# Acc_Comp.net
KiCad netlist of a schematic drawn in EAGLE
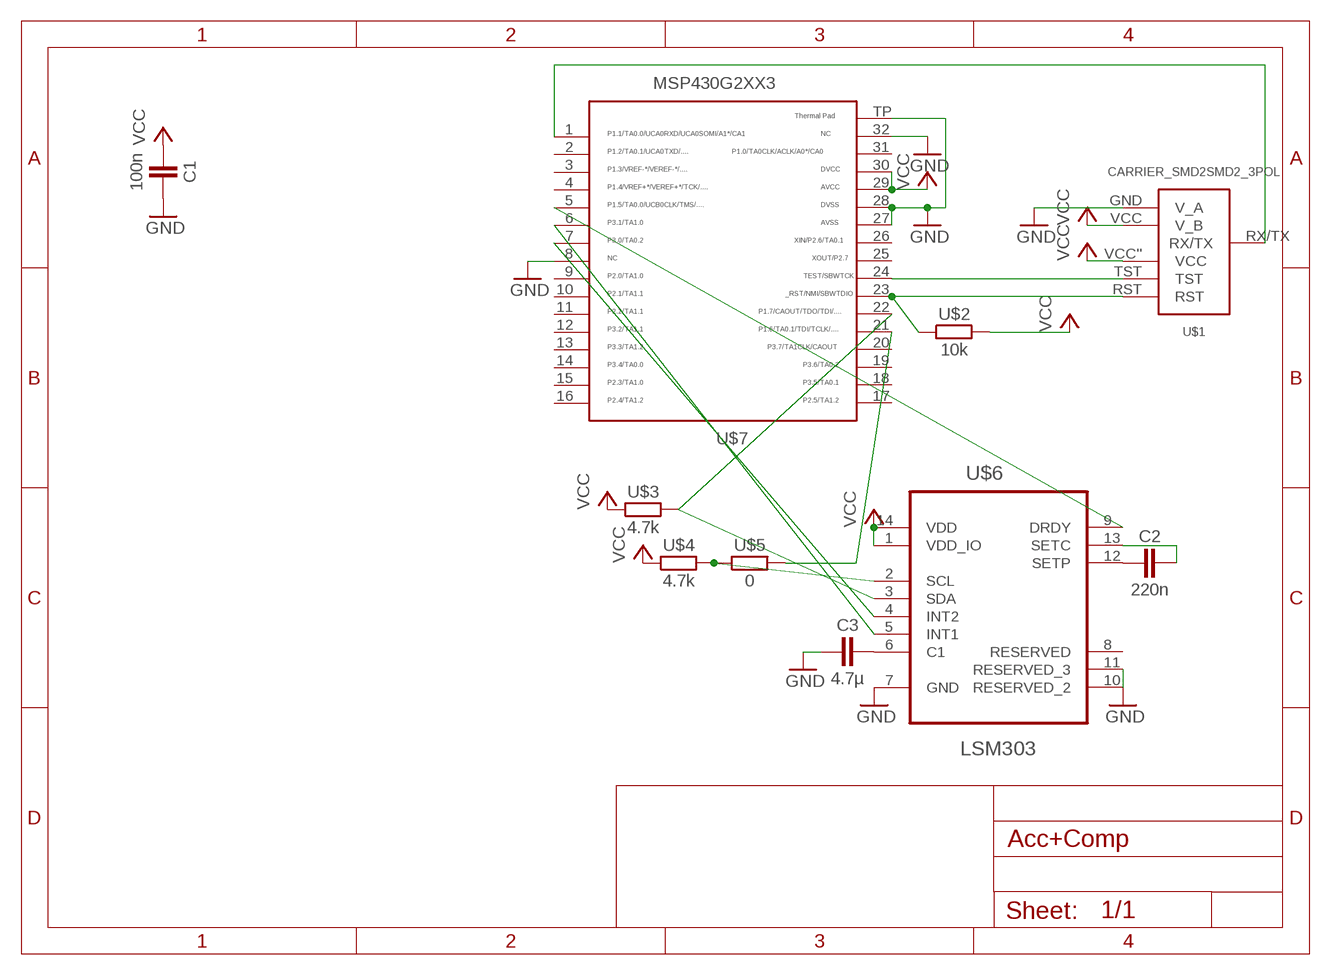
[diagram p0: schematic, sheet 1]

(export (version "E")
  (design (tool "Eeschema 10.0.6"))
  (components
    (comp (ref "C1")
      (value "100n")
      (footprint "eagle-import:603")
      (libsource (lib "eagle-import") (part "CAPACITOR"))
    )
    (comp (ref "C2")
      (value "220n")
      (footprint "eagle-import:603")
      (libsource (lib "eagle-import") (part "CAPACITOR"))
    )
    (comp (ref "C3")
      (value "4.7µ")
      (footprint "eagle-import:603")
      (libsource (lib "eagle-import") (part "CAPACITOR"))
    )
    (comp (ref "U$1")
      (value "CARRIER_SMD2SMD2_3POL")
      (footprint "eagle-import:CARRIER_SMD2_3POL")
      (libsource (lib "eagle-import") (part "CARRIER_SMD2SMD2_3POL"))
    )
    (comp (ref "U$2")
      (value "10k")
      (footprint "eagle-import:603")
      (libsource (lib "eagle-import") (part "RESISTOR0603"))
    )
    (comp (ref "U$3")
      (value "4.7k")
      (footprint "eagle-import:603")
      (libsource (lib "eagle-import") (part "RESISTOR0603"))
    )
    (comp (ref "U$4")
      (value "4.7k")
      (footprint "eagle-import:603")
      (libsource (lib "eagle-import") (part "RESISTOR0603"))
    )
    (comp (ref "U$5")
      (value "0")
      (footprint "eagle-import:603")
      (libsource (lib "eagle-import") (part "RESISTOR0603"))
    )
    (comp (ref "U$6")
      (value "LSM303")
      (footprint "eagle-import:LSM303")
      (libsource (lib "eagle-import") (part "LSM303"))
    )
    (comp (ref "U$7")
      (value "MSP430G2553")
      (footprint "eagle-import:QFN32")
      (libsource (lib "eagle-import") (part "MSP430G2553"))
    )
  )
  (nets
    (net (code "1") (name "GND") (class "Default")
      (node (ref "C1") (pin "2") (pinfunction "2_2") (pintype "passive"))
      (node (ref "C3") (pin "1") (pinfunction "1_1") (pintype "passive"))
      (node (ref "U$1") (pin "GND") (pinfunction "V_A_GND") (pintype "bidirectional"))
      (node (ref "U$6") (pin "10") (pinfunction "RESERVED_2_10") (pintype "passive"))
      (node (ref "U$6") (pin "11") (pinfunction "RESERVED_3_11") (pintype "passive"))
      (node (ref "U$6") (pin "7") (pinfunction "GND_7") (pintype "power_in"))
      (node (ref "U$7") (pin "27") (pinfunction "27_27") (pintype "bidirectional"))
      (node (ref "U$7") (pin "28") (pinfunction "28_28") (pintype "bidirectional"))
      (node (ref "U$7") (pin "32") (pinfunction "32_32") (pintype "bidirectional"))
      (node (ref "U$7") (pin "8") (pinfunction "8_8") (pintype "bidirectional"))
      (node (ref "U$7") (pin "TP") (pinfunction "TP_TP") (pintype "bidirectional"))
    )
    (net (code "2") (name "Net-(U$1-PadRST)") (class "Default")
      (node (ref "U$1") (pin "RST") (pinfunction "RST_RST") (pintype "bidirectional"))
      (node (ref "U$2") (pin "1") (pinfunction "1_1") (pintype "passive"))
      (node (ref "U$7") (pin "23") (pinfunction "23_23") (pintype "bidirectional"))
    )
    (net (code "3") (name "Net-(U$1-PadRX{slash}TX)") (class "Default")
      (node (ref "U$1") (pin "RX/TX") (pinfunction "RX/TX_RX/TX") (pintype "bidirectional"))
      (node (ref "U$7") (pin "1") (pinfunction "1_1") (pintype "bidirectional"))
    )
    (net (code "4") (name "Net-(U$1-PadTST)") (class "Default")
      (node (ref "U$1") (pin "TST") (pinfunction "TST_TST") (pintype "bidirectional"))
      (node (ref "U$7") (pin "24") (pinfunction "24_24") (pintype "bidirectional"))
    )
    (net (code "5") (name "Net-(U$5-Pad2)") (class "Default")
      (node (ref "U$5") (pin "2") (pinfunction "2_2") (pintype "passive"))
      (node (ref "U$7") (pin "21") (pinfunction "21_21") (pintype "bidirectional"))
    )
    (net (code "6") (name "Net-(U$6-C1)") (class "Default")
      (node (ref "C3") (pin "2") (pinfunction "2_2") (pintype "passive"))
      (node (ref "U$6") (pin "6") (pinfunction "C1_6") (pintype "passive"))
    )
    (net (code "7") (name "Net-(U$6-DRDY)") (class "Default")
      (node (ref "U$6") (pin "9") (pinfunction "DRDY_9") (pintype "passive"))
      (node (ref "U$7") (pin "5") (pinfunction "5_5") (pintype "bidirectional"))
    )
    (net (code "8") (name "Net-(U$6-INT1)") (class "Default")
      (node (ref "U$6") (pin "5") (pinfunction "INT1_5") (pintype "passive"))
      (node (ref "U$7") (pin "6") (pinfunction "6_6") (pintype "bidirectional"))
    )
    (net (code "9") (name "Net-(U$6-INT2)") (class "Default")
      (node (ref "U$6") (pin "4") (pinfunction "INT2_4") (pintype "passive"))
      (node (ref "U$7") (pin "7") (pinfunction "7_7") (pintype "bidirectional"))
    )
    (net (code "10") (name "Net-(U$6-SCL)") (class "Default")
      (node (ref "U$4") (pin "2") (pinfunction "2_2") (pintype "passive"))
      (node (ref "U$5") (pin "1") (pinfunction "1_1") (pintype "passive"))
      (node (ref "U$6") (pin "2") (pinfunction "SCL_2") (pintype "passive"))
    )
    (net (code "11") (name "Net-(U$6-SDA)") (class "Default")
      (node (ref "U$3") (pin "2") (pinfunction "2_2") (pintype "passive"))
      (node (ref "U$6") (pin "3") (pinfunction "SDA_3") (pintype "passive"))
      (node (ref "U$7") (pin "22") (pinfunction "22_22") (pintype "bidirectional"))
    )
    (net (code "12") (name "Net-(U$6-SETC)") (class "Default")
      (node (ref "C2") (pin "2") (pinfunction "2_2") (pintype "passive"))
      (node (ref "U$6") (pin "13") (pinfunction "SETC_13") (pintype "passive"))
    )
    (net (code "13") (name "Net-(U$6-SETP)") (class "Default")
      (node (ref "C2") (pin "1") (pinfunction "1_1") (pintype "passive"))
      (node (ref "U$6") (pin "12") (pinfunction "SETP_12") (pintype "passive"))
    )
    (net (code "14") (name "VCC") (class "Default")
      (node (ref "C1") (pin "1") (pinfunction "1_1") (pintype "passive"))
      (node (ref "U$1") (pin "VCC") (pinfunction "V_B_VCC") (pintype "bidirectional"))
      (node (ref "U$1") (pin "VCC''") (pinfunction "VCC_VCC''") (pintype "bidirectional"))
      (node (ref "U$2") (pin "2") (pinfunction "2_2") (pintype "passive"))
      (node (ref "U$3") (pin "1") (pinfunction "1_1") (pintype "passive"))
      (node (ref "U$4") (pin "1") (pinfunction "1_1") (pintype "passive"))
      (node (ref "U$6") (pin "1") (pinfunction "VDD_IO_1") (pintype "power_in"))
      (node (ref "U$6") (pin "14") (pinfunction "VDD_14") (pintype "power_in"))
      (node (ref "U$7") (pin "29") (pinfunction "29_29") (pintype "bidirectional"))
      (node (ref "U$7") (pin "30") (pinfunction "30_30") (pintype "bidirectional"))
    )
    (net (code "15") (name "unconnected-(U$6-RESERVED-Pad8)") (class "Default")
      (node (ref "U$6") (pin "8") (pinfunction "RESERVED_8") (pintype "passive"))
    )
    (net (code "16") (name "unconnected-(U$7-Pad2)") (class "Default")
      (node (ref "U$7") (pin "2") (pinfunction "2_2") (pintype "bidirectional"))
    )
    (net (code "17") (name "unconnected-(U$7-Pad3)") (class "Default")
      (node (ref "U$7") (pin "3") (pinfunction "3_3") (pintype "bidirectional"))
    )
    (net (code "18") (name "unconnected-(U$7-Pad4)") (class "Default")
      (node (ref "U$7") (pin "4") (pinfunction "4_4") (pintype "bidirectional"))
    )
    (net (code "19") (name "unconnected-(U$7-Pad9)") (class "Default")
      (node (ref "U$7") (pin "9") (pinfunction "9_9") (pintype "bidirectional"))
    )
    (net (code "20") (name "unconnected-(U$7-Pad10)") (class "Default")
      (node (ref "U$7") (pin "10") (pinfunction "10_10") (pintype "bidirectional"))
    )
    (net (code "21") (name "unconnected-(U$7-Pad11)") (class "Default")
      (node (ref "U$7") (pin "11") (pinfunction "11_11") (pintype "bidirectional"))
    )
    (net (code "22") (name "unconnected-(U$7-Pad12)") (class "Default")
      (node (ref "U$7") (pin "12") (pinfunction "12_12") (pintype "bidirectional"))
    )
    (net (code "23") (name "unconnected-(U$7-Pad13)") (class "Default")
      (node (ref "U$7") (pin "13") (pinfunction "13_13") (pintype "bidirectional"))
    )
    (net (code "24") (name "unconnected-(U$7-Pad14)") (class "Default")
      (node (ref "U$7") (pin "14") (pinfunction "14_14") (pintype "bidirectional"))
    )
    (net (code "25") (name "unconnected-(U$7-Pad15)") (class "Default")
      (node (ref "U$7") (pin "15") (pinfunction "15_15") (pintype "bidirectional"))
    )
    (net (code "26") (name "unconnected-(U$7-Pad16)") (class "Default")
      (node (ref "U$7") (pin "16") (pinfunction "16_16") (pintype "bidirectional"))
    )
    (net (code "27") (name "unconnected-(U$7-Pad17)") (class "Default")
      (node (ref "U$7") (pin "17") (pinfunction "17_17") (pintype "bidirectional"))
    )
    (net (code "28") (name "unconnected-(U$7-Pad18)") (class "Default")
      (node (ref "U$7") (pin "18") (pinfunction "18_18") (pintype "bidirectional"))
    )
    (net (code "29") (name "unconnected-(U$7-Pad19)") (class "Default")
      (node (ref "U$7") (pin "19") (pinfunction "19_19") (pintype "bidirectional"))
    )
    (net (code "30") (name "unconnected-(U$7-Pad20)") (class "Default")
      (node (ref "U$7") (pin "20") (pinfunction "20_20") (pintype "bidirectional"))
    )
    (net (code "31") (name "unconnected-(U$7-Pad25)") (class "Default")
      (node (ref "U$7") (pin "25") (pinfunction "25_25") (pintype "bidirectional"))
    )
    (net (code "32") (name "unconnected-(U$7-Pad26)") (class "Default")
      (node (ref "U$7") (pin "26") (pinfunction "26_26") (pintype "bidirectional"))
    )
    (net (code "33") (name "unconnected-(U$7-Pad31)") (class "Default")
      (node (ref "U$7") (pin "31") (pinfunction "31_31") (pintype "bidirectional"))
    )
  )
)
